# PWM_Board.net
KiCad netlist of a schematic drawn in EAGLE
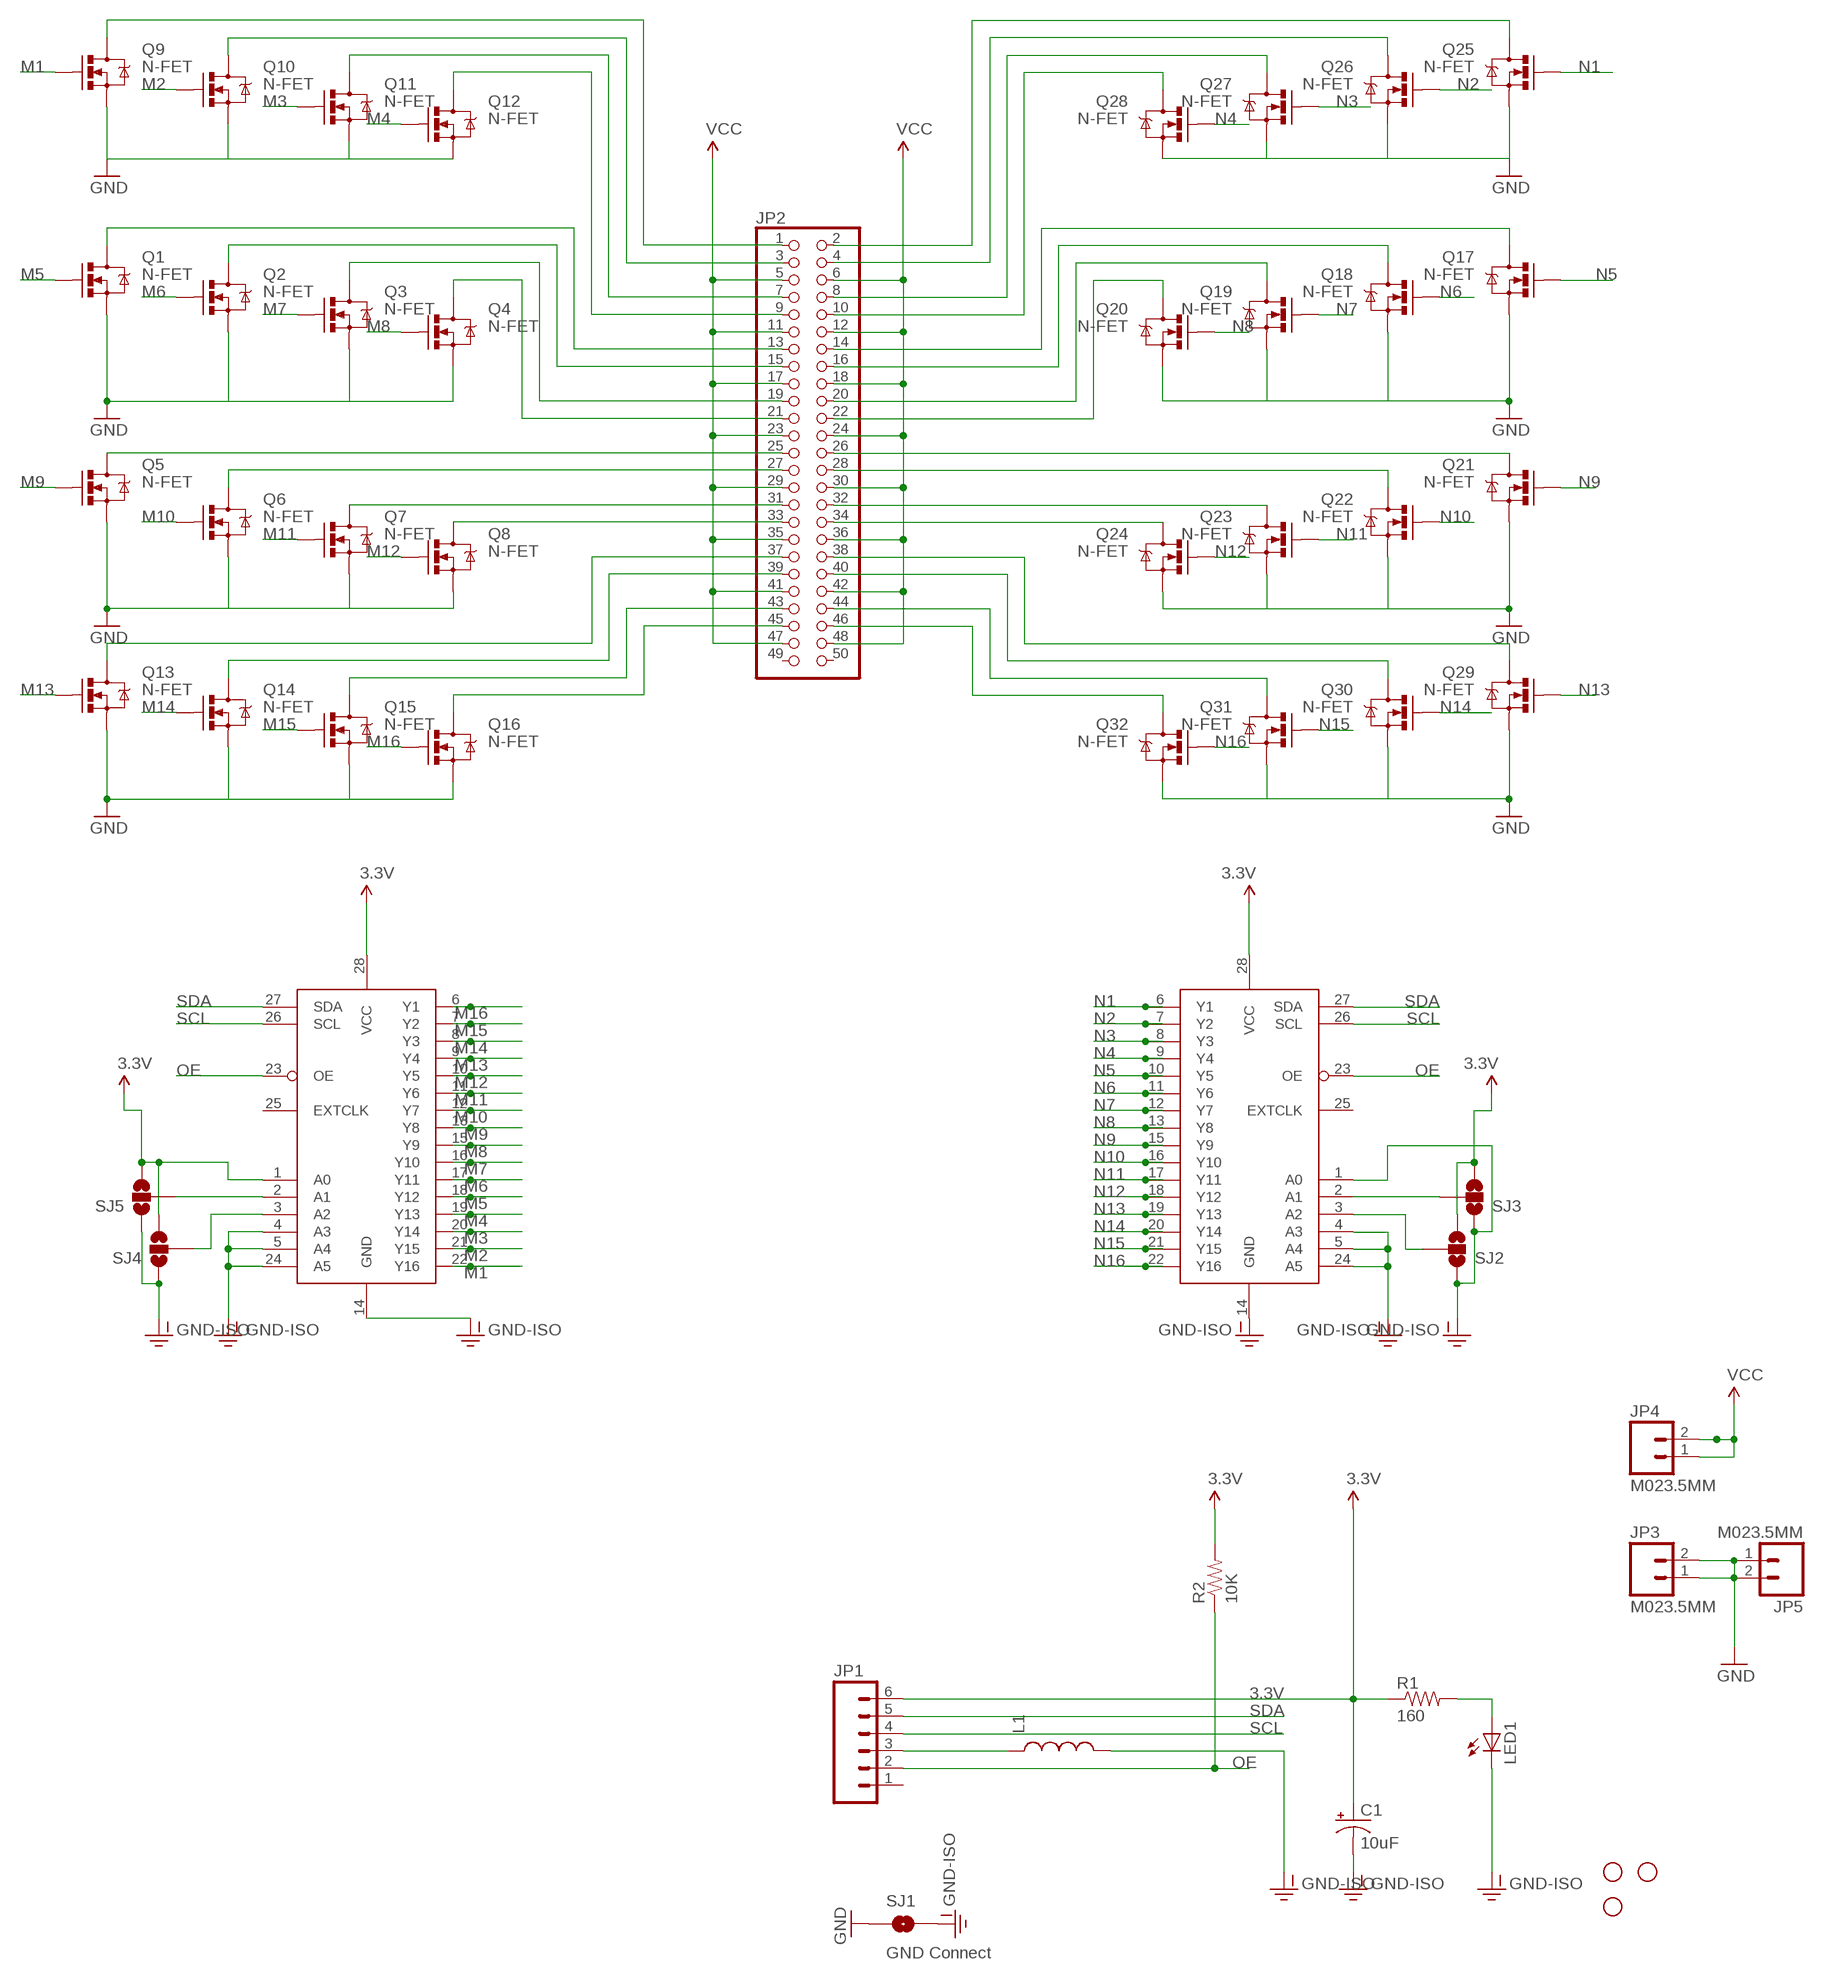
[diagram p0: schematic, sheet 1]

(export (version "E")
  (design (tool "Eeschema 10.0.6"))
  (components
    (comp (ref "C1")
      (value "10uF")
      (footprint "eagle-import:EIA3216")
      (libsource (lib "eagle-import") (part "CAP_POL1206"))
    )
    (comp (ref "JP1")
      (value "M06POLAR")
      (footprint "eagle-import:MOLEX-1X6")
      (libsource (lib "eagle-import") (part "M06POLAR"))
    )
    (comp (ref "JP2")
      (value "PINHD-2X25")
      (footprint "eagle-import:2X25")
      (libsource (lib "eagle-import") (part "PINHD-2X25"))
    )
    (comp (ref "JP3")
      (value "M023.5MM")
      (footprint "eagle-import:SCREWTERMINAL-3.5MM-2")
      (libsource (lib "eagle-import") (part "M023.5MM"))
    )
    (comp (ref "JP4")
      (value "M023.5MM")
      (footprint "eagle-import:SCREWTERMINAL-3.5MM-2")
      (libsource (lib "eagle-import") (part "M023.5MM"))
    )
    (comp (ref "JP5")
      (value "M023.5MM")
      (footprint "eagle-import:SCREWTERMINAL-3.5MM-2")
      (libsource (lib "eagle-import") (part "M023.5MM"))
    )
    (comp (ref "L1")
      (value "INDUCTOR1206H*")
      (footprint "eagle-import:INDUCTOR-1206")
      (libsource (lib "eagle-import") (part "INDUCTORH1206"))
    )
    (comp (ref "LED1")
      (value "LED-FKIT-1206")
      (footprint "eagle-import:FKIT-LED-1206")
      (libsource (lib "eagle-import") (part "LED-FKIT-1206"))
    )
    (comp (ref "Q1")
      (value "N-FET")
      (footprint "eagle-import:SOT23")
      (libsource (lib "eagle-import") (part "MOSFET-NCHANNELBSS138"))
    )
    (comp (ref "Q2")
      (value "N-FET")
      (footprint "eagle-import:SOT23")
      (libsource (lib "eagle-import") (part "MOSFET-NCHANNELBSS138"))
    )
    (comp (ref "Q3")
      (value "N-FET")
      (footprint "eagle-import:SOT23")
      (libsource (lib "eagle-import") (part "MOSFET-NCHANNELBSS138"))
    )
    (comp (ref "Q4")
      (value "N-FET")
      (footprint "eagle-import:SOT23")
      (libsource (lib "eagle-import") (part "MOSFET-NCHANNELBSS138"))
    )
    (comp (ref "Q5")
      (value "N-FET")
      (footprint "eagle-import:SOT23")
      (libsource (lib "eagle-import") (part "MOSFET-NCHANNELBSS138"))
    )
    (comp (ref "Q6")
      (value "N-FET")
      (footprint "eagle-import:SOT23")
      (libsource (lib "eagle-import") (part "MOSFET-NCHANNELBSS138"))
    )
    (comp (ref "Q7")
      (value "N-FET")
      (footprint "eagle-import:SOT23")
      (libsource (lib "eagle-import") (part "MOSFET-NCHANNELBSS138"))
    )
    (comp (ref "Q8")
      (value "N-FET")
      (footprint "eagle-import:SOT23")
      (libsource (lib "eagle-import") (part "MOSFET-NCHANNELBSS138"))
    )
    (comp (ref "Q9")
      (value "N-FET")
      (footprint "eagle-import:SOT23")
      (libsource (lib "eagle-import") (part "MOSFET-NCHANNELBSS138"))
    )
    (comp (ref "Q10")
      (value "N-FET")
      (footprint "eagle-import:SOT23")
      (libsource (lib "eagle-import") (part "MOSFET-NCHANNELBSS138"))
    )
    (comp (ref "Q11")
      (value "N-FET")
      (footprint "eagle-import:SOT23")
      (libsource (lib "eagle-import") (part "MOSFET-NCHANNELBSS138"))
    )
    (comp (ref "Q12")
      (value "N-FET")
      (footprint "eagle-import:SOT23")
      (libsource (lib "eagle-import") (part "MOSFET-NCHANNELBSS138"))
    )
    (comp (ref "Q13")
      (value "N-FET")
      (footprint "eagle-import:SOT23")
      (libsource (lib "eagle-import") (part "MOSFET-NCHANNELBSS138"))
    )
    (comp (ref "Q14")
      (value "N-FET")
      (footprint "eagle-import:SOT23")
      (libsource (lib "eagle-import") (part "MOSFET-NCHANNELBSS138"))
    )
    (comp (ref "Q15")
      (value "N-FET")
      (footprint "eagle-import:SOT23")
      (libsource (lib "eagle-import") (part "MOSFET-NCHANNELBSS138"))
    )
    (comp (ref "Q16")
      (value "N-FET")
      (footprint "eagle-import:SOT23")
      (libsource (lib "eagle-import") (part "MOSFET-NCHANNELBSS138"))
    )
    (comp (ref "Q17")
      (value "N-FET")
      (footprint "eagle-import:SOT23")
      (libsource (lib "eagle-import") (part "MOSFET-NCHANNELBSS138"))
    )
    (comp (ref "Q18")
      (value "N-FET")
      (footprint "eagle-import:SOT23")
      (libsource (lib "eagle-import") (part "MOSFET-NCHANNELBSS138"))
    )
    (comp (ref "Q19")
      (value "N-FET")
      (footprint "eagle-import:SOT23")
      (libsource (lib "eagle-import") (part "MOSFET-NCHANNELBSS138"))
    )
    (comp (ref "Q20")
      (value "N-FET")
      (footprint "eagle-import:SOT23")
      (libsource (lib "eagle-import") (part "MOSFET-NCHANNELBSS138"))
    )
    (comp (ref "Q21")
      (value "N-FET")
      (footprint "eagle-import:SOT23")
      (libsource (lib "eagle-import") (part "MOSFET-NCHANNELBSS138"))
    )
    (comp (ref "Q22")
      (value "N-FET")
      (footprint "eagle-import:SOT23")
      (libsource (lib "eagle-import") (part "MOSFET-NCHANNELBSS138"))
    )
    (comp (ref "Q23")
      (value "N-FET")
      (footprint "eagle-import:SOT23")
      (libsource (lib "eagle-import") (part "MOSFET-NCHANNELBSS138"))
    )
    (comp (ref "Q24")
      (value "N-FET")
      (footprint "eagle-import:SOT23")
      (libsource (lib "eagle-import") (part "MOSFET-NCHANNELBSS138"))
    )
    (comp (ref "Q25")
      (value "N-FET")
      (footprint "eagle-import:SOT23")
      (libsource (lib "eagle-import") (part "MOSFET-NCHANNELBSS138"))
    )
    (comp (ref "Q26")
      (value "N-FET")
      (footprint "eagle-import:SOT23")
      (libsource (lib "eagle-import") (part "MOSFET-NCHANNELBSS138"))
    )
    (comp (ref "Q27")
      (value "N-FET")
      (footprint "eagle-import:SOT23")
      (libsource (lib "eagle-import") (part "MOSFET-NCHANNELBSS138"))
    )
    (comp (ref "Q28")
      (value "N-FET")
      (footprint "eagle-import:SOT23")
      (libsource (lib "eagle-import") (part "MOSFET-NCHANNELBSS138"))
    )
    (comp (ref "Q29")
      (value "N-FET")
      (footprint "eagle-import:SOT23")
      (libsource (lib "eagle-import") (part "MOSFET-NCHANNELBSS138"))
    )
    (comp (ref "Q30")
      (value "N-FET")
      (footprint "eagle-import:SOT23")
      (libsource (lib "eagle-import") (part "MOSFET-NCHANNELBSS138"))
    )
    (comp (ref "Q31")
      (value "N-FET")
      (footprint "eagle-import:SOT23")
      (libsource (lib "eagle-import") (part "MOSFET-NCHANNELBSS138"))
    )
    (comp (ref "Q32")
      (value "N-FET")
      (footprint "eagle-import:SOT23")
      (libsource (lib "eagle-import") (part "MOSFET-NCHANNELBSS138"))
    )
    (comp (ref "R1")
      (value "160")
      (footprint "eagle-import:1206")
      (libsource (lib "eagle-import") (part "RESISTOR1206"))
    )
    (comp (ref "R2")
      (value "10K")
      (footprint "eagle-import:1206")
      (libsource (lib "eagle-import") (part "RESISTOR1206"))
    )
    (comp (ref "SJ1")
      (value "GND Connect")
      (footprint "eagle-import:SJ_2S")
      (libsource (lib "eagle-import") (part "SOLDERJUMPERNC"))
    )
    (comp (ref "SJ2")
      (value "SOLDERJUMPER_2WAYS")
      (footprint "eagle-import:SJ_3")
      (libsource (lib "eagle-import") (part "SOLDERJUMPER_2WAYS"))
    )
    (comp (ref "SJ3")
      (value "SOLDERJUMPER_2WAYS")
      (footprint "eagle-import:SJ_3")
      (libsource (lib "eagle-import") (part "SOLDERJUMPER_2WAYS"))
    )
    (comp (ref "SJ4")
      (value "SOLDERJUMPER_2WAYS")
      (footprint "eagle-import:SJ_3")
      (libsource (lib "eagle-import") (part "SOLDERJUMPER_2WAYS"))
    )
    (comp (ref "SJ5")
      (value "SOLDERJUMPER_2WAYS")
      (footprint "eagle-import:SJ_3")
      (libsource (lib "eagle-import") (part "SOLDERJUMPER_2WAYS"))
    )
    (comp (ref "STANDOFF1")
      (value "STAND-OFF")
      (footprint "eagle-import:STAND-OFF")
      (libsource (lib "eagle-import") (part "STAND-OFF"))
    )
    (comp (ref "STANDOFF3")
      (value "STAND-OFF")
      (footprint "eagle-import:STAND-OFF")
      (libsource (lib "eagle-import") (part "STAND-OFF"))
    )
    (comp (ref "STANDOFF4")
      (value "STAND-OFF")
      (footprint "eagle-import:STAND-OFF")
      (libsource (lib "eagle-import") (part "STAND-OFF"))
    )
    (comp (ref "U$2")
      (value "PCA9685")
      (footprint "eagle-import:TSSOP28")
      (libsource (lib "eagle-import") (part "PCA9685"))
    )
    (comp (ref "U$3")
      (value "PCA9685")
      (footprint "eagle-import:TSSOP28")
      (libsource (lib "eagle-import") (part "PCA9685"))
    )
  )
  (nets
    (net (code "1") (name "/M1") (class "Default")
      (node (ref "Q9") (pin "1") (pinfunction "G_1") (pintype "passive"))
      (node (ref "U$3") (pin "22") (pinfunction "Y16_22") (pintype "bidirectional"))
    )
    (net (code "2") (name "/M2") (class "Default")
      (node (ref "Q10") (pin "1") (pinfunction "G_1") (pintype "passive"))
      (node (ref "U$3") (pin "21") (pinfunction "Y15_21") (pintype "bidirectional"))
    )
    (net (code "3") (name "/M3") (class "Default")
      (node (ref "Q11") (pin "1") (pinfunction "G_1") (pintype "passive"))
      (node (ref "U$3") (pin "20") (pinfunction "Y14_20") (pintype "bidirectional"))
    )
    (net (code "4") (name "/M4") (class "Default")
      (node (ref "Q12") (pin "1") (pinfunction "G_1") (pintype "passive"))
      (node (ref "U$3") (pin "19") (pinfunction "Y13_19") (pintype "bidirectional"))
    )
    (net (code "5") (name "/M5") (class "Default")
      (node (ref "Q1") (pin "1") (pinfunction "G_1") (pintype "passive"))
      (node (ref "U$3") (pin "18") (pinfunction "Y12_18") (pintype "bidirectional"))
    )
    (net (code "6") (name "/M6") (class "Default")
      (node (ref "Q2") (pin "1") (pinfunction "G_1") (pintype "passive"))
      (node (ref "U$3") (pin "17") (pinfunction "Y11_17") (pintype "bidirectional"))
    )
    (net (code "7") (name "/M7") (class "Default")
      (node (ref "Q3") (pin "1") (pinfunction "G_1") (pintype "passive"))
      (node (ref "U$3") (pin "16") (pinfunction "Y10_16") (pintype "bidirectional"))
    )
    (net (code "8") (name "/M8") (class "Default")
      (node (ref "Q4") (pin "1") (pinfunction "G_1") (pintype "passive"))
      (node (ref "U$3") (pin "15") (pinfunction "Y9_15") (pintype "bidirectional"))
    )
    (net (code "9") (name "/M9") (class "Default")
      (node (ref "Q5") (pin "1") (pinfunction "G_1") (pintype "passive"))
      (node (ref "U$3") (pin "13") (pinfunction "Y8_13") (pintype "bidirectional"))
    )
    (net (code "10") (name "/M10") (class "Default")
      (node (ref "Q6") (pin "1") (pinfunction "G_1") (pintype "passive"))
      (node (ref "U$3") (pin "12") (pinfunction "Y7_12") (pintype "bidirectional"))
    )
    (net (code "11") (name "/M11") (class "Default")
      (node (ref "Q7") (pin "1") (pinfunction "G_1") (pintype "passive"))
      (node (ref "U$3") (pin "11") (pinfunction "Y6_11") (pintype "bidirectional"))
    )
    (net (code "12") (name "/M12") (class "Default")
      (node (ref "Q8") (pin "1") (pinfunction "G_1") (pintype "passive"))
      (node (ref "U$3") (pin "10") (pinfunction "Y5_10") (pintype "bidirectional"))
    )
    (net (code "13") (name "/M13") (class "Default")
      (node (ref "Q13") (pin "1") (pinfunction "G_1") (pintype "passive"))
      (node (ref "U$3") (pin "9") (pinfunction "Y4_9") (pintype "bidirectional"))
    )
    (net (code "14") (name "/M14") (class "Default")
      (node (ref "Q14") (pin "1") (pinfunction "G_1") (pintype "passive"))
      (node (ref "U$3") (pin "8") (pinfunction "Y3_8") (pintype "bidirectional"))
    )
    (net (code "15") (name "/M15") (class "Default")
      (node (ref "Q15") (pin "1") (pinfunction "G_1") (pintype "passive"))
      (node (ref "U$3") (pin "7") (pinfunction "Y2_7") (pintype "bidirectional"))
    )
    (net (code "16") (name "/M16") (class "Default")
      (node (ref "Q16") (pin "1") (pinfunction "G_1") (pintype "passive"))
      (node (ref "U$3") (pin "6") (pinfunction "Y1_6") (pintype "bidirectional"))
    )
    (net (code "17") (name "/N1") (class "Default")
      (node (ref "Q25") (pin "1") (pinfunction "G_1") (pintype "passive"))
      (node (ref "U$2") (pin "6") (pinfunction "Y1_6") (pintype "bidirectional"))
    )
    (net (code "18") (name "/N2") (class "Default")
      (node (ref "Q26") (pin "1") (pinfunction "G_1") (pintype "passive"))
      (node (ref "U$2") (pin "7") (pinfunction "Y2_7") (pintype "bidirectional"))
    )
    (net (code "19") (name "/N3") (class "Default")
      (node (ref "Q27") (pin "1") (pinfunction "G_1") (pintype "passive"))
      (node (ref "U$2") (pin "8") (pinfunction "Y3_8") (pintype "bidirectional"))
    )
    (net (code "20") (name "/N4") (class "Default")
      (node (ref "Q28") (pin "1") (pinfunction "G_1") (pintype "passive"))
      (node (ref "U$2") (pin "9") (pinfunction "Y4_9") (pintype "bidirectional"))
    )
    (net (code "21") (name "/N5") (class "Default")
      (node (ref "Q17") (pin "1") (pinfunction "G_1") (pintype "passive"))
      (node (ref "U$2") (pin "10") (pinfunction "Y5_10") (pintype "bidirectional"))
    )
    (net (code "22") (name "/N6") (class "Default")
      (node (ref "Q18") (pin "1") (pinfunction "G_1") (pintype "passive"))
      (node (ref "U$2") (pin "11") (pinfunction "Y6_11") (pintype "bidirectional"))
    )
    (net (code "23") (name "/N7") (class "Default")
      (node (ref "Q19") (pin "1") (pinfunction "G_1") (pintype "passive"))
      (node (ref "U$2") (pin "12") (pinfunction "Y7_12") (pintype "bidirectional"))
    )
    (net (code "24") (name "/N8") (class "Default")
      (node (ref "Q20") (pin "1") (pinfunction "G_1") (pintype "passive"))
      (node (ref "U$2") (pin "13") (pinfunction "Y8_13") (pintype "bidirectional"))
    )
    (net (code "25") (name "/N9") (class "Default")
      (node (ref "Q21") (pin "1") (pinfunction "G_1") (pintype "passive"))
      (node (ref "U$2") (pin "15") (pinfunction "Y9_15") (pintype "bidirectional"))
    )
    (net (code "26") (name "/N10") (class "Default")
      (node (ref "Q22") (pin "1") (pinfunction "G_1") (pintype "passive"))
      (node (ref "U$2") (pin "16") (pinfunction "Y10_16") (pintype "bidirectional"))
    )
    (net (code "27") (name "/N11") (class "Default")
      (node (ref "Q23") (pin "1") (pinfunction "G_1") (pintype "passive"))
      (node (ref "U$2") (pin "17") (pinfunction "Y11_17") (pintype "bidirectional"))
    )
    (net (code "28") (name "/N12") (class "Default")
      (node (ref "Q24") (pin "1") (pinfunction "G_1") (pintype "passive"))
      (node (ref "U$2") (pin "18") (pinfunction "Y12_18") (pintype "bidirectional"))
    )
    (net (code "29") (name "/N13") (class "Default")
      (node (ref "Q29") (pin "1") (pinfunction "G_1") (pintype "passive"))
      (node (ref "U$2") (pin "19") (pinfunction "Y13_19") (pintype "bidirectional"))
    )
    (net (code "30") (name "/N14") (class "Default")
      (node (ref "Q30") (pin "1") (pinfunction "G_1") (pintype "passive"))
      (node (ref "U$2") (pin "20") (pinfunction "Y14_20") (pintype "bidirectional"))
    )
    (net (code "31") (name "/N15") (class "Default")
      (node (ref "Q31") (pin "1") (pinfunction "G_1") (pintype "passive"))
      (node (ref "U$2") (pin "21") (pinfunction "Y15_21") (pintype "bidirectional"))
    )
    (net (code "32") (name "/N16") (class "Default")
      (node (ref "Q32") (pin "1") (pinfunction "G_1") (pintype "passive"))
      (node (ref "U$2") (pin "22") (pinfunction "Y16_22") (pintype "bidirectional"))
    )
    (net (code "33") (name "/OE") (class "Default")
      (node (ref "JP1") (pin "2") (pinfunction "2_2") (pintype "passive"))
      (node (ref "R2") (pin "1") (pinfunction "1_1") (pintype "passive"))
      (node (ref "U$2") (pin "23") (pinfunction "OE_23") (pintype "bidirectional"))
      (node (ref "U$3") (pin "23") (pinfunction "OE_23") (pintype "bidirectional"))
    )
    (net (code "34") (name "/SCL") (class "Default")
      (node (ref "JP1") (pin "4") (pinfunction "4_4") (pintype "passive"))
      (node (ref "U$2") (pin "26") (pinfunction "SCL_26") (pintype "bidirectional"))
      (node (ref "U$3") (pin "26") (pinfunction "SCL_26") (pintype "bidirectional"))
    )
    (net (code "35") (name "/SDA") (class "Default")
      (node (ref "JP1") (pin "5") (pinfunction "5_5") (pintype "passive"))
      (node (ref "U$2") (pin "27") (pinfunction "SDA_27") (pintype "bidirectional"))
      (node (ref "U$3") (pin "27") (pinfunction "SDA_27") (pintype "bidirectional"))
    )
    (net (code "36") (name "3.3V") (class "Default")
      (node (ref "C1") (pin "A") (pinfunction "+_A") (pintype "passive"))
      (node (ref "JP1") (pin "6") (pinfunction "6_6") (pintype "passive"))
      (node (ref "R1") (pin "1") (pinfunction "1_1") (pintype "passive"))
      (node (ref "R2") (pin "2") (pinfunction "2_2") (pintype "passive"))
      (node (ref "SJ2") (pin "3") (pinfunction "3_3") (pintype "passive"))
      (node (ref "SJ3") (pin "3") (pinfunction "3_3") (pintype "passive"))
      (node (ref "SJ4") (pin "3") (pinfunction "3_3") (pintype "passive"))
      (node (ref "SJ5") (pin "3") (pinfunction "3_3") (pintype "passive"))
      (node (ref "U$2") (pin "28") (pinfunction "VCC_28") (pintype "bidirectional"))
      (node (ref "U$3") (pin "1") (pinfunction "A0_1") (pintype "bidirectional"))
      (node (ref "U$3") (pin "28") (pinfunction "VCC_28") (pintype "bidirectional"))
    )
    (net (code "37") (name "GND") (class "Default")
      (node (ref "JP3") (pin "1") (pinfunction "1_1") (pintype "passive"))
      (node (ref "JP3") (pin "2") (pinfunction "2_2") (pintype "passive"))
      (node (ref "JP5") (pin "1") (pinfunction "1_1") (pintype "passive"))
      (node (ref "JP5") (pin "2") (pinfunction "2_2") (pintype "passive"))
      (node (ref "Q1") (pin "2") (pinfunction "S_2") (pintype "passive"))
      (node (ref "Q10") (pin "2") (pinfunction "S_2") (pintype "passive"))
      (node (ref "Q11") (pin "2") (pinfunction "S_2") (pintype "passive"))
      (node (ref "Q12") (pin "2") (pinfunction "S_2") (pintype "passive"))
      (node (ref "Q13") (pin "2") (pinfunction "S_2") (pintype "passive"))
      (node (ref "Q14") (pin "2") (pinfunction "S_2") (pintype "passive"))
      (node (ref "Q15") (pin "2") (pinfunction "S_2") (pintype "passive"))
      (node (ref "Q16") (pin "2") (pinfunction "S_2") (pintype "passive"))
      (node (ref "Q17") (pin "2") (pinfunction "S_2") (pintype "passive"))
      (node (ref "Q18") (pin "2") (pinfunction "S_2") (pintype "passive"))
      (node (ref "Q19") (pin "2") (pinfunction "S_2") (pintype "passive"))
      (node (ref "Q2") (pin "2") (pinfunction "S_2") (pintype "passive"))
      (node (ref "Q20") (pin "2") (pinfunction "S_2") (pintype "passive"))
      (node (ref "Q21") (pin "2") (pinfunction "S_2") (pintype "passive"))
      (node (ref "Q22") (pin "2") (pinfunction "S_2") (pintype "passive"))
      (node (ref "Q23") (pin "2") (pinfunction "S_2") (pintype "passive"))
      (node (ref "Q24") (pin "2") (pinfunction "S_2") (pintype "passive"))
      (node (ref "Q25") (pin "2") (pinfunction "S_2") (pintype "passive"))
      (node (ref "Q26") (pin "2") (pinfunction "S_2") (pintype "passive"))
      (node (ref "Q27") (pin "2") (pinfunction "S_2") (pintype "passive"))
      (node (ref "Q28") (pin "2") (pinfunction "S_2") (pintype "passive"))
      (node (ref "Q29") (pin "2") (pinfunction "S_2") (pintype "passive"))
      (node (ref "Q3") (pin "2") (pinfunction "S_2") (pintype "passive"))
      (node (ref "Q30") (pin "2") (pinfunction "S_2") (pintype "passive"))
      (node (ref "Q31") (pin "2") (pinfunction "S_2") (pintype "passive"))
      (node (ref "Q32") (pin "2") (pinfunction "S_2") (pintype "passive"))
      (node (ref "Q4") (pin "2") (pinfunction "S_2") (pintype "passive"))
      (node (ref "Q5") (pin "2") (pinfunction "S_2") (pintype "passive"))
      (node (ref "Q6") (pin "2") (pinfunction "S_2") (pintype "passive"))
      (node (ref "Q7") (pin "2") (pinfunction "S_2") (pintype "passive"))
      (node (ref "Q8") (pin "2") (pinfunction "S_2") (pintype "passive"))
      (node (ref "Q9") (pin "2") (pinfunction "S_2") (pintype "passive"))
      (node (ref "SJ1") (pin "1") (pinfunction "1_1") (pintype "passive"))
    )
    (net (code "38") (name "GND-ISO") (class "Default")
      (node (ref "C1") (pin "C") (pinfunction "-_C") (pintype "passive"))
      (node (ref "L1") (pin "P$2") (pinfunction "2_P$2") (pintype "passive"))
      (node (ref "LED1") (pin "C") (pinfunction "C_C") (pintype "passive"))
      (node (ref "SJ1") (pin "2") (pinfunction "2_2") (pintype "passive"))
      (node (ref "SJ2") (pin "1") (pinfunction "1_1") (pintype "passive"))
      (node (ref "SJ3") (pin "1") (pinfunction "1_1") (pintype "passive"))
      (node (ref "SJ4") (pin "1") (pinfunction "1_1") (pintype "passive"))
      (node (ref "SJ5") (pin "1") (pinfunction "1_1") (pintype "passive"))
      (node (ref "U$2") (pin "1") (pinfunction "A0_1") (pintype "bidirectional"))
      (node (ref "U$2") (pin "14") (pinfunction "GND_14") (pintype "bidirectional"))
      (node (ref "U$2") (pin "24") (pinfunction "A5_24") (pintype "bidirectional"))
      (node (ref "U$2") (pin "4") (pinfunction "A3_4") (pintype "bidirectional"))
      (node (ref "U$2") (pin "5") (pinfunction "A4_5") (pintype "bidirectional"))
      (node (ref "U$3") (pin "14") (pinfunction "GND_14") (pintype "bidirectional"))
      (node (ref "U$3") (pin "24") (pinfunction "A5_24") (pintype "bidirectional"))
      (node (ref "U$3") (pin "4") (pinfunction "A3_4") (pintype "bidirectional"))
      (node (ref "U$3") (pin "5") (pinfunction "A4_5") (pintype "bidirectional"))
    )
    (net (code "39") (name "Net-(L1-1)") (class "Default")
      (node (ref "JP1") (pin "3") (pinfunction "3_3") (pintype "passive"))
      (node (ref "L1") (pin "P$1") (pinfunction "1_P$1") (pintype "passive"))
    )
    (net (code "40") (name "Net-(LED1-PadA)") (class "Default")
      (node (ref "LED1") (pin "A") (pinfunction "A_A") (pintype "passive"))
      (node (ref "R1") (pin "2") (pinfunction "2_2") (pintype "passive"))
    )
    (net (code "41") (name "Net-(Q1-D)") (class "Default")
      (node (ref "JP2") (pin "13") (pinfunction "13_13") (pintype "passive"))
      (node (ref "Q1") (pin "3") (pinfunction "D_3") (pintype "passive"))
    )
    (net (code "42") (name "Net-(Q2-D)") (class "Default")
      (node (ref "JP2") (pin "15") (pinfunction "15_15") (pintype "passive"))
      (node (ref "Q2") (pin "3") (pinfunction "D_3") (pintype "passive"))
    )
    (net (code "43") (name "Net-(Q3-D)") (class "Default")
      (node (ref "JP2") (pin "19") (pinfunction "19_19") (pintype "passive"))
      (node (ref "Q3") (pin "3") (pinfunction "D_3") (pintype "passive"))
    )
    (net (code "44") (name "Net-(Q4-D)") (class "Default")
      (node (ref "JP2") (pin "21") (pinfunction "21_21") (pintype "passive"))
      (node (ref "Q4") (pin "3") (pinfunction "D_3") (pintype "passive"))
    )
    (net (code "45") (name "Net-(Q5-D)") (class "Default")
      (node (ref "JP2") (pin "25") (pinfunction "25_25") (pintype "passive"))
      (node (ref "Q5") (pin "3") (pinfunction "D_3") (pintype "passive"))
    )
    (net (code "46") (name "Net-(Q6-D)") (class "Default")
      (node (ref "JP2") (pin "27") (pinfunction "27_27") (pintype "passive"))
      (node (ref "Q6") (pin "3") (pinfunction "D_3") (pintype "passive"))
    )
    (net (code "47") (name "Net-(Q7-D)") (class "Default")
      (node (ref "JP2") (pin "31") (pinfunction "31_31") (pintype "passive"))
      (node (ref "Q7") (pin "3") (pinfunction "D_3") (pintype "passive"))
    )
    (net (code "48") (name "Net-(Q8-D)") (class "Default")
      (node (ref "JP2") (pin "33") (pinfunction "33_33") (pintype "passive"))
      (node (ref "Q8") (pin "3") (pinfunction "D_3") (pintype "passive"))
    )
    (net (code "49") (name "Net-(Q9-D)") (class "Default")
      (node (ref "JP2") (pin "1") (pinfunction "1_1") (pintype "passive"))
      (node (ref "Q9") (pin "3") (pinfunction "D_3") (pintype "passive"))
    )
    (net (code "50") (name "Net-(Q10-D)") (class "Default")
      (node (ref "JP2") (pin "3") (pinfunction "3_3") (pintype "passive"))
      (node (ref "Q10") (pin "3") (pinfunction "D_3") (pintype "passive"))
    )
    (net (code "51") (name "Net-(Q11-D)") (class "Default")
      (node (ref "JP2") (pin "7") (pinfunction "7_7") (pintype "passive"))
      (node (ref "Q11") (pin "3") (pinfunction "D_3") (pintype "passive"))
    )
    (net (code "52") (name "Net-(Q12-D)") (class "Default")
      (node (ref "JP2") (pin "9") (pinfunction "9_9") (pintype "passive"))
      (node (ref "Q12") (pin "3") (pinfunction "D_3") (pintype "passive"))
    )
    (net (code "53") (name "Net-(Q13-D)") (class "Default")
      (node (ref "JP2") (pin "37") (pinfunction "37_37") (pintype "passive"))
      (node (ref "Q13") (pin "3") (pinfunction "D_3") (pintype "passive"))
    )
    (net (code "54") (name "Net-(Q14-D)") (class "Default")
      (node (ref "JP2") (pin "39") (pinfunction "39_39") (pintype "passive"))
      (node (ref "Q14") (pin "3") (pinfunction "D_3") (pintype "passive"))
    )
    (net (code "55") (name "Net-(Q15-D)") (class "Default")
      (node (ref "JP2") (pin "43") (pinfunction "43_43") (pintype "passive"))
      (node (ref "Q15") (pin "3") (pinfunction "D_3") (pintype "passive"))
    )
    (net (code "56") (name "Net-(Q16-D)") (class "Default")
      (node (ref "JP2") (pin "45") (pinfunction "45_45") (pintype "passive"))
      (node (ref "Q16") (pin "3") (pinfunction "D_3") (pintype "passive"))
    )
    (net (code "57") (name "Net-(Q17-D)") (class "Default")
      (node (ref "JP2") (pin "14") (pinfunction "14_14") (pintype "passive"))
      (node (ref "Q17") (pin "3") (pinfunction "D_3") (pintype "passive"))
    )
    (net (code "58") (name "Net-(Q18-D)") (class "Default")
      (node (ref "JP2") (pin "16") (pinfunction "16_16") (pintype "passive"))
      (node (ref "Q18") (pin "3") (pinfunction "D_3") (pintype "passive"))
    )
    (net (code "59") (name "Net-(Q19-D)") (class "Default")
      (node (ref "JP2") (pin "20") (pinfunction "20_20") (pintype "passive"))
      (node (ref "Q19") (pin "3") (pinfunction "D_3") (pintype "passive"))
    )
    (net (code "60") (name "Net-(Q20-D)") (class "Default")
      (node (ref "JP2") (pin "22") (pinfunction "22_22") (pintype "passive"))
      (node (ref "Q20") (pin "3") (pinfunction "D_3") (pintype "passive"))
    )
    (net (code "61") (name "Net-(Q21-D)") (class "Default")
      (node (ref "JP2") (pin "26") (pinfunction "26_26") (pintype "passive"))
      (node (ref "Q21") (pin "3") (pinfunction "D_3") (pintype "passive"))
    )
    (net (code "62") (name "Net-(Q22-D)") (class "Default")
      (node (ref "JP2") (pin "28") (pinfunction "28_28") (pintype "passive"))
      (node (ref "Q22") (pin "3") (pinfunction "D_3") (pintype "passive"))
    )
    (net (code "63") (name "Net-(Q23-D)") (class "Default")
      (node (ref "JP2") (pin "32") (pinfunction "32_32") (pintype "passive"))
      (node (ref "Q23") (pin "3") (pinfunction "D_3") (pintype "passive"))
    )
    (net (code "64") (name "Net-(Q24-D)") (class "Default")
      (node (ref "JP2") (pin "34") (pinfunction "34_34") (pintype "passive"))
      (node (ref "Q24") (pin "3") (pinfunction "D_3") (pintype "passive"))
    )
    (net (code "65") (name "Net-(Q25-D)") (class "Default")
      (node (ref "JP2") (pin "2") (pinfunction "2_2") (pintype "passive"))
      (node (ref "Q25") (pin "3") (pinfunction "D_3") (pintype "passive"))
    )
    (net (code "66") (name "Net-(Q26-D)") (class "Default")
      (node (ref "JP2") (pin "4") (pinfunction "4_4") (pintype "passive"))
      (node (ref "Q26") (pin "3") (pinfunction "D_3") (pintype "passive"))
    )
    (net (code "67") (name "Net-(Q27-D)") (class "Default")
      (node (ref "JP2") (pin "8") (pinfunction "8_8") (pintype "passive"))
      (node (ref "Q27") (pin "3") (pinfunction "D_3") (pintype "passive"))
    )
    (net (code "68") (name "Net-(Q28-D)") (class "Default")
      (node (ref "JP2") (pin "10") (pinfunction "10_10") (pintype "passive"))
      (node (ref "Q28") (pin "3") (pinfunction "D_3") (pintype "passive"))
    )
    (net (code "69") (name "Net-(Q29-D)") (class "Default")
      (node (ref "JP2") (pin "38") (pinfunction "38_38") (pintype "passive"))
      (node (ref "Q29") (pin "3") (pinfunction "D_3") (pintype "passive"))
    )
    (net (code "70") (name "Net-(Q30-D)") (class "Default")
      (node (ref "JP2") (pin "40") (pinfunction "40_40") (pintype "passive"))
      (node (ref "Q30") (pin "3") (pinfunction "D_3") (pintype "passive"))
    )
    (net (code "71") (name "Net-(Q31-D)") (class "Default")
      (node (ref "JP2") (pin "44") (pinfunction "44_44") (pintype "passive"))
      (node (ref "Q31") (pin "3") (pinfunction "D_3") (pintype "passive"))
    )
    (net (code "72") (name "Net-(Q32-D)") (class "Default")
      (node (ref "JP2") (pin "46") (pinfunction "46_46") (pintype "passive"))
      (node (ref "Q32") (pin "3") (pinfunction "D_3") (pintype "passive"))
    )
    (net (code "73") (name "Net-(U$2-A1)") (class "Default")
      (node (ref "SJ3") (pin "2") (pinfunction "2_2") (pintype "passive"))
      (node (ref "U$2") (pin "2") (pinfunction "A1_2") (pintype "bidirectional"))
    )
    (net (code "74") (name "Net-(U$2-A2)") (class "Default")
      (node (ref "SJ2") (pin "2") (pinfunction "2_2") (pintype "passive"))
      (node (ref "U$2") (pin "3") (pinfunction "A2_3") (pintype "bidirectional"))
    )
    (net (code "75") (name "Net-(U$3-A1)") (class "Default")
      (node (ref "SJ5") (pin "2") (pinfunction "2_2") (pintype "passive"))
      (node (ref "U$3") (pin "2") (pinfunction "A1_2") (pintype "bidirectional"))
    )
    (net (code "76") (name "Net-(U$3-A2)") (class "Default")
      (node (ref "SJ4") (pin "2") (pinfunction "2_2") (pintype "passive"))
      (node (ref "U$3") (pin "3") (pinfunction "A2_3") (pintype "bidirectional"))
    )
    (net (code "77") (name "VCC") (class "Default")
      (node (ref "JP2") (pin "11") (pinfunction "11_11") (pintype "passive"))
      (node (ref "JP2") (pin "12") (pinfunction "12_12") (pintype "passive"))
      (node (ref "JP2") (pin "17") (pinfunction "17_17") (pintype "passive"))
      (node (ref "JP2") (pin "18") (pinfunction "18_18") (pintype "passive"))
      (node (ref "JP2") (pin "23") (pinfunction "23_23") (pintype "passive"))
      (node (ref "JP2") (pin "24") (pinfunction "24_24") (pintype "passive"))
      (node (ref "JP2") (pin "29") (pinfunction "29_29") (pintype "passive"))
      (node (ref "JP2") (pin "30") (pinfunction "30_30") (pintype "passive"))
      (node (ref "JP2") (pin "35") (pinfunction "35_35") (pintype "passive"))
      (node (ref "JP2") (pin "36") (pinfunction "36_36") (pintype "passive"))
      (node (ref "JP2") (pin "41") (pinfunction "41_41") (pintype "passive"))
      (node (ref "JP2") (pin "42") (pinfunction "42_42") (pintype "passive"))
      (node (ref "JP2") (pin "47") (pinfunction "47_47") (pintype "passive"))
      (node (ref "JP2") (pin "48") (pinfunction "48_48") (pintype "passive"))
      (node (ref "JP2") (pin "5") (pinfunction "5_5") (pintype "passive"))
      (node (ref "JP2") (pin "6") (pinfunction "6_6") (pintype "passive"))
      (node (ref "JP4") (pin "1") (pinfunction "1_1") (pintype "passive"))
      (node (ref "JP4") (pin "2") (pinfunction "2_2") (pintype "passive"))
    )
    (net (code "78") (name "unconnected-(JP1-Pad1)") (class "Default")
      (node (ref "JP1") (pin "1") (pinfunction "1_1") (pintype "passive"))
    )
    (net (code "79") (name "unconnected-(JP2-Pad49)") (class "Default")
      (node (ref "JP2") (pin "49") (pinfunction "49_49") (pintype "passive"))
    )
    (net (code "80") (name "unconnected-(JP2-Pad50)") (class "Default")
      (node (ref "JP2") (pin "50") (pinfunction "50_50") (pintype "passive"))
    )
    (net (code "81") (name "unconnected-(U$2-EXTCLK-Pad25)") (class "Default")
      (node (ref "U$2") (pin "25") (pinfunction "EXTCLK_25") (pintype "bidirectional"))
    )
    (net (code "82") (name "unconnected-(U$3-EXTCLK-Pad25)") (class "Default")
      (node (ref "U$3") (pin "25") (pinfunction "EXTCLK_25") (pintype "bidirectional"))
    )
  )
)
